# Side_1_v1_1.net
KiCad netlist of a schematic drawn in EAGLE
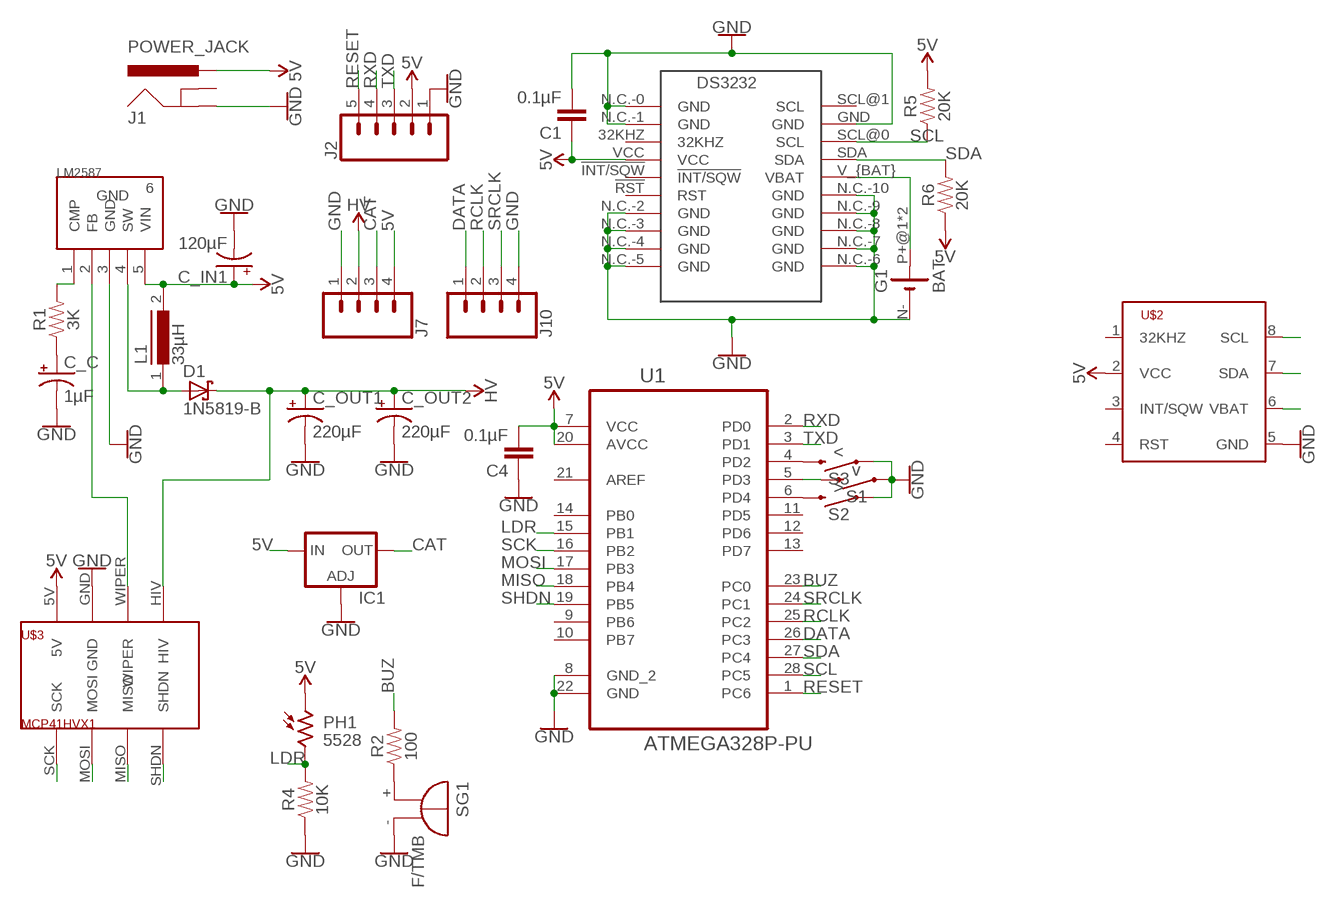
[diagram p0: schematic, sheet 1]

(export (version "E")
  (design (tool "Eeschema 10.0.6"))
  (components
    (comp (ref "C1")
      (value "0.1µF")
      (footprint "eagle-import:CAP-0.1I")
      (libsource (lib "eagle-import") (part "0.1µF-0.1''"))
    )
    (comp (ref "C4")
      (value "0.1µF")
      (footprint "eagle-import:CAP-0.1I")
      (libsource (lib "eagle-import") (part "0.1µF-0.1''"))
    )
    (comp (ref "C_C")
      (value "1µF")
      (footprint "eagle-import:CAP_POL_2MM")
      (libsource (lib "eagle-import") (part "CAP_POL_1µF"))
    )
    (comp (ref "C_IN1")
      (value "120µF")
      (footprint "eagle-import:CAP_POL_3MM")
      (libsource (lib "eagle-import") (part "CAP_POL_120µF"))
    )
    (comp (ref "C_OUT1")
      (value "220µF")
      (footprint "eagle-import:CPOL-RADIAL-5MM-10MM")
      (libsource (lib "eagle-import") (part "1000UF-RADIAL-5MM-25V-20%"))
    )
    (comp (ref "C_OUT2")
      (value "220µF")
      (footprint "eagle-import:CPOL-RADIAL-5MM-10MM")
      (libsource (lib "eagle-import") (part "1000UF-RADIAL-5MM-25V-20%"))
    )
    (comp (ref "D1")
      (value "1N5819-B")
      (footprint "eagle-import:DO41-7.6")
      (libsource (lib "eagle-import") (part "1N5819-B"))
    )
    (comp (ref "G1")
      (value "BAT")
      (footprint "eagle-import:CELL_RETAINER_11.6MM")
      (fields (field (name "MF") "KEYSTONE") (field (name "MPN") "2997"))
      (libsource (lib "eagle-import") (part "BATTERY-HOLDER_11.6MM"))
    )
    (comp (ref "IC1")
      (value "LM317TS")
      (footprint "eagle-import:317TS")
      (libsource (lib "eagle-import") (part "LM317TS"))
    )
    (comp (ref "J1")
      (value "POWER_JACK")
      (footprint "eagle-import:POWER_JACK_PTH")
      (libsource (lib "eagle-import") (part "POWER_JACK"))
    )
    (comp (ref "J2")
      (value "CONN_05")
      (footprint "eagle-import:1X05")
      (libsource (lib "eagle-import") (part "CONN_05"))
    )
    (comp (ref "J7")
      (value "CONN_04")
      (footprint "eagle-import:1X04")
      (libsource (lib "eagle-import") (part "CONN_04"))
    )
    (comp (ref "J10")
      (value "CONN_04")
      (footprint "eagle-import:1X04")
      (libsource (lib "eagle-import") (part "CONN_04"))
    )
    (comp (ref "L1")
      (value "33µH")
      (footprint "eagle-import:MICC12")
      (libsource (lib "eagle-import") (part "MICC12"))
    )
    (comp (ref "LM2587")
      (value "LM2587S")
      (footprint "eagle-import:TO263-5")
      (libsource (lib "eagle-import") (part "LM2587S"))
    )
    (comp (ref "PH1")
      (value "5528")
      (footprint "eagle-import:5528")
      (libsource (lib "eagle-import") (part "5528"))
    )
    (comp (ref "R1")
      (value "3K")
      (footprint "eagle-import:AXIAL-0.3")
      (libsource (lib "eagle-import") (part "RESISTORAXIAL-0.3"))
    )
    (comp (ref "R2")
      (value "100")
      (footprint "eagle-import:AXIAL-0.3")
      (libsource (lib "eagle-import") (part "RESISTORAXIAL-0.3"))
    )
    (comp (ref "R4")
      (value "10K")
      (footprint "eagle-import:AXIAL-0.3")
      (libsource (lib "eagle-import") (part "RESISTORAXIAL-0.3"))
    )
    (comp (ref "R5")
      (value "20K")
      (footprint "eagle-import:AXIAL-0.3")
      (libsource (lib "eagle-import") (part "RESISTORAXIAL-0.3"))
    )
    (comp (ref "R6")
      (value "20K")
      (footprint "eagle-import:AXIAL-0.3")
      (libsource (lib "eagle-import") (part "RESISTORAXIAL-0.3"))
    )
    (comp (ref "S1")
      (value "v")
      (footprint "eagle-import:TACTILE_SWITCH_PTH_6.0MM")
      (libsource (lib "eagle-import") (part "MOMENTARY-SWITCH-SPST-PTH-6.0MM"))
    )
    (comp (ref "S2")
      (value ">")
      (footprint "eagle-import:TACTILE_SWITCH_PTH_6.0MM")
      (libsource (lib "eagle-import") (part "MOMENTARY-SWITCH-SPST-PTH-6.0MM"))
    )
    (comp (ref "S3")
      (value "<")
      (footprint "eagle-import:TACTILE_SWITCH_PTH_6.0MM")
      (libsource (lib "eagle-import") (part "MOMENTARY-SWITCH-SPST-PTH-6.0MM"))
    )
    (comp (ref "SG1")
      (value "F/TMB")
      (footprint "eagle-import:F_TMB")
      (libsource (lib "eagle-import") (part "F/TMB"))
    )
    (comp (ref "U$1")
      (value "DS3232")
      (footprint "eagle-import:SO20-2")
      (libsource (lib "eagle-import") (part "DS3232"))
    )
    (comp (ref "U$2")
      (value "DS3232M")
      (footprint "eagle-import:SO8")
      (libsource (lib "eagle-import") (part "DS3232M"))
    )
    (comp (ref "U$3")
      (value "MCP41HVX1")
      (footprint "eagle-import:MCP41HVX1_BREAKOUT")
      (libsource (lib "eagle-import") (part "MCP41HVX1_BREAKOUT"))
    )
    (comp (ref "U1")
      (value "ATMEGA328P-PU")
      (footprint "eagle-import:DIP254P762X457-28")
      (libsource (lib "eagle-import") (part "ATMEGA328P-PU"))
    )
  )
  (nets
    (net (code "1") (name "/BAT") (class "Default")
      (node (ref "G1") (pin "P+@1") (pinfunction "+_P+@1") (pintype "passive"))
      (node (ref "G1") (pin "P+@2") (pinfunction "+_P+@2") (pintype "passive"))
      (node (ref "U$1") (pin "V_{BAT}") (pinfunction "VBAT_V_{BAT}") (pintype "bidirectional"))
      (node (ref "U$2") (pin "6") (pinfunction "VBAT_6") (pintype "bidirectional"))
    )
    (net (code "2") (name "/BUZ") (class "Default")
      (node (ref "R2") (pin "P$2") (pinfunction "2_P$2") (pintype "passive"))
      (node (ref "U1") (pin "23") (pinfunction "PC0_23") (pintype "bidirectional"))
    )
    (net (code "3") (name "/CAT") (class "Default")
      (node (ref "IC1") (pin "2") (pinfunction "OUT_2") (pintype "passive"))
      (node (ref "J7") (pin "3") (pinfunction "3_3") (pintype "passive"))
    )
    (net (code "4") (name "/DATA") (class "Default")
      (node (ref "J10") (pin "1") (pinfunction "1_1") (pintype "passive"))
      (node (ref "U1") (pin "26") (pinfunction "PC3_26") (pintype "bidirectional"))
    )
    (net (code "5") (name "/LDR") (class "Default")
      (node (ref "PH1") (pin "2") (pinfunction "2_2") (pintype "passive"))
      (node (ref "R4") (pin "P$2") (pinfunction "2_P$2") (pintype "passive"))
      (node (ref "U1") (pin "15") (pinfunction "PB1_15") (pintype "bidirectional"))
    )
    (net (code "6") (name "/MISO") (class "Default")
      (node (ref "U$3") (pin "MISO") (pinfunction "MISO_MISO") (pintype "bidirectional"))
      (node (ref "U1") (pin "18") (pinfunction "PB4_18") (pintype "bidirectional"))
    )
    (net (code "7") (name "/MOSI") (class "Default")
      (node (ref "U$3") (pin "MOSI") (pinfunction "MOSI_MOSI") (pintype "bidirectional"))
      (node (ref "U1") (pin "17") (pinfunction "PB3_17") (pintype "bidirectional"))
    )
    (net (code "8") (name "/RCLK") (class "Default")
      (node (ref "J10") (pin "2") (pinfunction "2_2") (pintype "passive"))
      (node (ref "U1") (pin "25") (pinfunction "PC2_25") (pintype "bidirectional"))
    )
    (net (code "9") (name "/RESET") (class "Default")
      (node (ref "J2") (pin "5") (pinfunction "5_5") (pintype "passive"))
      (node (ref "U1") (pin "1") (pinfunction "PC6_1") (pintype "bidirectional"))
    )
    (net (code "10") (name "/RXD") (class "Default")
      (node (ref "J2") (pin "4") (pinfunction "4_4") (pintype "passive"))
      (node (ref "U1") (pin "2") (pinfunction "PD0_2") (pintype "bidirectional"))
    )
    (net (code "11") (name "/SCK") (class "Default")
      (node (ref "U$3") (pin "SCK") (pinfunction "SCK_SCK") (pintype "bidirectional"))
      (node (ref "U1") (pin "16") (pinfunction "PB2_16") (pintype "bidirectional"))
    )
    (net (code "12") (name "/SCL") (class "Default")
      (node (ref "R5") (pin "P$1") (pinfunction "1_P$1") (pintype "passive"))
      (node (ref "U$1") (pin "SCL@0") (pinfunction "SCL_SCL@0") (pintype "bidirectional"))
      (node (ref "U$2") (pin "8") (pinfunction "SCL_8") (pintype "bidirectional"))
      (node (ref "U1") (pin "28") (pinfunction "PC5_28") (pintype "bidirectional"))
    )
    (net (code "13") (name "/SDA") (class "Default")
      (node (ref "R6") (pin "P$2") (pinfunction "2_P$2") (pintype "passive"))
      (node (ref "U$1") (pin "SDA") (pinfunction "SDA_SDA") (pintype "bidirectional"))
      (node (ref "U$2") (pin "7") (pinfunction "SDA_7") (pintype "bidirectional"))
      (node (ref "U1") (pin "27") (pinfunction "PC4_27") (pintype "bidirectional"))
    )
    (net (code "14") (name "/SHDN") (class "Default")
      (node (ref "U$3") (pin "SHDN") (pinfunction "SHDN_SHDN") (pintype "bidirectional"))
      (node (ref "U1") (pin "19") (pinfunction "PB5_19") (pintype "bidirectional"))
    )
    (net (code "15") (name "/SRCLK") (class "Default")
      (node (ref "J10") (pin "3") (pinfunction "3_3") (pintype "passive"))
      (node (ref "U1") (pin "24") (pinfunction "PC1_24") (pintype "bidirectional"))
    )
    (net (code "16") (name "/TXD") (class "Default")
      (node (ref "J2") (pin "3") (pinfunction "3_3") (pintype "passive"))
      (node (ref "U1") (pin "3") (pinfunction "PD1_3") (pintype "bidirectional"))
    )
    (net (code "17") (name "5V") (class "Default")
      (node (ref "C1") (pin "1") (pinfunction "1_1") (pintype "passive"))
      (node (ref "C4") (pin "2") (pinfunction "2_2") (pintype "passive"))
      (node (ref "C_IN1") (pin "POS") (pinfunction "+_POS") (pintype "passive"))
      (node (ref "IC1") (pin "3") (pinfunction "IN_3") (pintype "input"))
      (node (ref "J1") (pin "PWR") (pinfunction "PWR_PWR") (pintype "bidirectional"))
      (node (ref "J2") (pin "2") (pinfunction "2_2") (pintype "passive"))
      (node (ref "J7") (pin "4") (pinfunction "4_4") (pintype "passive"))
      (node (ref "L1") (pin "2") (pinfunction "2_2") (pintype "passive"))
      (node (ref "LM2587") (pin "5") (pinfunction "VIN_5") (pintype "bidirectional"))
      (node (ref "PH1") (pin "1") (pinfunction "1_1") (pintype "passive"))
      (node (ref "R5") (pin "P$2") (pinfunction "2_P$2") (pintype "passive"))
      (node (ref "R6") (pin "P$1") (pinfunction "1_P$1") (pintype "passive"))
      (node (ref "U$1") (pin "VCC") (pinfunction "VCC_VCC") (pintype "bidirectional"))
      (node (ref "U$2") (pin "2") (pinfunction "VCC_2") (pintype "bidirectional"))
      (node (ref "U$3") (pin "5V") (pinfunction "5V_5V") (pintype "bidirectional"))
      (node (ref "U1") (pin "20") (pinfunction "AVCC_20") (pintype "power_in"))
      (node (ref "U1") (pin "7") (pinfunction "VCC_7") (pintype "power_in"))
    )
    (net (code "18") (name "GND") (class "Default")
      (node (ref "C1") (pin "2") (pinfunction "2_2") (pintype "passive"))
      (node (ref "C4") (pin "1") (pinfunction "1_1") (pintype "passive"))
      (node (ref "C_C") (pin "NEG") (pinfunction "-_NEG") (pintype "passive"))
      (node (ref "C_IN1") (pin "NEG") (pinfunction "-_NEG") (pintype "passive"))
      (node (ref "C_OUT1") (pin "-") (pinfunction "-_-") (pintype "passive"))
      (node (ref "C_OUT2") (pin "-") (pinfunction "-_-") (pintype "passive"))
      (node (ref "G1") (pin "N-") (pinfunction "-_N-") (pintype "passive"))
      (node (ref "IC1") (pin "1") (pinfunction "ADJ_1") (pintype "input"))
      (node (ref "J1") (pin "GND") (pinfunction "GND_GND") (pintype "bidirectional"))
      (node (ref "J10") (pin "4") (pinfunction "4_4") (pintype "passive"))
      (node (ref "J2") (pin "1") (pinfunction "1_1") (pintype "passive"))
      (node (ref "J7") (pin "1") (pinfunction "1_1") (pintype "passive"))
      (node (ref "LM2587") (pin "3") (pinfunction "GND_3") (pintype "bidirectional"))
      (node (ref "R4") (pin "P$1") (pinfunction "1_P$1") (pintype "passive"))
      (node (ref "S1") (pin "1") (pinfunction "1_1") (pintype "passive"))
      (node (ref "S2") (pin "1") (pinfunction "1_1") (pintype "passive"))
      (node (ref "S3") (pin "1") (pinfunction "1_1") (pintype "passive"))
      (node (ref "SG1") (pin "-") (pinfunction "-_-") (pintype "passive"))
      (node (ref "U$1") (pin "GND") (pinfunction "GND_GND") (pintype "bidirectional"))
      (node (ref "U$1") (pin "N.C.-0") (pinfunction "GND_N.C.-0") (pintype "bidirectional"))
      (node (ref "U$1") (pin "N.C.-1") (pinfunction "GND_N.C.-1") (pintype "bidirectional"))
      (node (ref "U$1") (pin "N.C.-10") (pinfunction "GND_N.C.-10") (pintype "bidirectional"))
      (node (ref "U$1") (pin "N.C.-2") (pinfunction "GND_N.C.-2") (pintype "bidirectional"))
      (node (ref "U$1") (pin "N.C.-3") (pinfunction "GND_N.C.-3") (pintype "bidirectional"))
      (node (ref "U$1") (pin "N.C.-4") (pinfunction "GND_N.C.-4") (pintype "bidirectional"))
      (node (ref "U$1") (pin "N.C.-5") (pinfunction "GND_N.C.-5") (pintype "bidirectional"))
      (node (ref "U$1") (pin "N.C.-6") (pinfunction "GND_N.C.-6") (pintype "bidirectional"))
      (node (ref "U$1") (pin "N.C.-7") (pinfunction "GND_N.C.-7") (pintype "bidirectional"))
      (node (ref "U$1") (pin "N.C.-8") (pinfunction "GND_N.C.-8") (pintype "bidirectional"))
      (node (ref "U$1") (pin "N.C.-9") (pinfunction "GND_N.C.-9") (pintype "bidirectional"))
      (node (ref "U$2") (pin "5") (pinfunction "GND_5") (pintype "bidirectional"))
      (node (ref "U$3") (pin "GND") (pinfunction "GND_GND") (pintype "bidirectional"))
      (node (ref "U1") (pin "22") (pinfunction "GND_22") (pintype "passive"))
      (node (ref "U1") (pin "8") (pinfunction "GND_2_8") (pintype "passive"))
    )
    (net (code "19") (name "HV") (class "Default")
      (node (ref "C_OUT1") (pin "+") (pinfunction "+_+") (pintype "passive"))
      (node (ref "C_OUT2") (pin "+") (pinfunction "+_+") (pintype "passive"))
      (node (ref "D1") (pin "C") (pinfunction "C_C") (pintype "passive"))
      (node (ref "J7") (pin "2") (pinfunction "2_2") (pintype "passive"))
      (node (ref "U$3") (pin "HIV") (pinfunction "HIV_HIV") (pintype "bidirectional"))
    )
    (net (code "20") (name "Net-(C_C-+)") (class "Default")
      (node (ref "C_C") (pin "POS") (pinfunction "+_POS") (pintype "passive"))
      (node (ref "R1") (pin "P$1") (pinfunction "1_P$1") (pintype "passive"))
    )
    (net (code "21") (name "Net-(LM2587-CMP)") (class "Default")
      (node (ref "LM2587") (pin "1") (pinfunction "CMP_1") (pintype "bidirectional"))
      (node (ref "R1") (pin "P$2") (pinfunction "2_P$2") (pintype "passive"))
    )
    (net (code "22") (name "Net-(LM2587-FB)") (class "Default")
      (node (ref "LM2587") (pin "2") (pinfunction "FB_2") (pintype "bidirectional"))
      (node (ref "U$3") (pin "WIPER") (pinfunction "WIPER_WIPER") (pintype "bidirectional"))
    )
    (net (code "23") (name "Net-(LM2587-SW)") (class "Default")
      (node (ref "D1") (pin "A") (pinfunction "A_A") (pintype "passive"))
      (node (ref "L1") (pin "1") (pinfunction "1_1") (pintype "passive"))
      (node (ref "LM2587") (pin "4") (pinfunction "SW_4") (pintype "bidirectional"))
    )
    (net (code "24") (name "Net-(R2-1)") (class "Default")
      (node (ref "R2") (pin "P$1") (pinfunction "1_P$1") (pintype "passive"))
      (node (ref "SG1") (pin "+") (pinfunction "+_+") (pintype "passive"))
    )
    (net (code "25") (name "Net-(S1-2)") (class "Default")
      (node (ref "S1") (pin "3") (pinfunction "2_3") (pintype "passive"))
      (node (ref "U1") (pin "5") (pinfunction "PD3_5") (pintype "bidirectional"))
    )
    (net (code "26") (name "Net-(S2-2)") (class "Default")
      (node (ref "S2") (pin "3") (pinfunction "2_3") (pintype "passive"))
      (node (ref "U1") (pin "6") (pinfunction "PD4_6") (pintype "bidirectional"))
    )
    (net (code "27") (name "Net-(S3-2)") (class "Default")
      (node (ref "S3") (pin "3") (pinfunction "2_3") (pintype "passive"))
      (node (ref "U1") (pin "4") (pinfunction "PD2_4") (pintype "bidirectional"))
    )
    (net (code "28") (name "unconnected-(J1-PadGNDBREAK)") (class "Default")
      (node (ref "J1") (pin "GNDBREAK") (pinfunction "GNDBREAK_GNDBREAK") (pintype "bidirectional"))
    )
    (net (code "29") (name "unconnected-(LM2587-GND-Pad6)") (class "Default")
      (node (ref "LM2587") (pin "6") (pinfunction "GND_6") (pintype "bidirectional"))
    )
    (net (code "30") (name "unconnected-(U$1-Pad32KHZ)") (class "Default")
      (node (ref "U$1") (pin "32KHZ") (pinfunction "32KHZ_32KHZ") (pintype "bidirectional"))
    )
    (net (code "31") (name "unconnected-(U$1-RST-Pad!RST)") (class "Default")
      (node (ref "U$1") (pin "!RST") (pinfunction "RST_!RST") (pintype "bidirectional"))
    )
    (net (code "32") (name "unconnected-(U$1-SCL-PadSCL@1)") (class "Default")
      (node (ref "U$1") (pin "SCL@1") (pinfunction "SCL_SCL@1") (pintype "bidirectional"))
    )
    (net (code "33") (name "unconnected-(U$1-~{INT{slash}SQW}-Pad!INT{slash}SQW)") (class "Default")
      (node (ref "U$1") (pin "!INT/SQW") (pinfunction "~{INT/SQW}_!INT/SQW") (pintype "bidirectional"))
    )
    (net (code "34") (name "unconnected-(U$2-32KHZ-Pad1)") (class "Default")
      (node (ref "U$2") (pin "1") (pinfunction "32KHZ_1") (pintype "bidirectional"))
    )
    (net (code "35") (name "unconnected-(U$2-INT{slash}SQW-Pad3)") (class "Default")
      (node (ref "U$2") (pin "3") (pinfunction "INT/SQW_3") (pintype "bidirectional"))
    )
    (net (code "36") (name "unconnected-(U$2-RST-Pad4)") (class "Default")
      (node (ref "U$2") (pin "4") (pinfunction "RST_4") (pintype "bidirectional"))
    )
    (net (code "37") (name "unconnected-(U1-AREF-Pad21)") (class "Default")
      (node (ref "U1") (pin "21") (pinfunction "AREF_21") (pintype "input"))
    )
    (net (code "38") (name "unconnected-(U1-PB0-Pad14)") (class "Default")
      (node (ref "U1") (pin "14") (pinfunction "PB0_14") (pintype "bidirectional"))
    )
    (net (code "39") (name "unconnected-(U1-PB6-Pad9)") (class "Default")
      (node (ref "U1") (pin "9") (pinfunction "PB6_9") (pintype "bidirectional"))
    )
    (net (code "40") (name "unconnected-(U1-PB7-Pad10)") (class "Default")
      (node (ref "U1") (pin "10") (pinfunction "PB7_10") (pintype "bidirectional"))
    )
    (net (code "41") (name "unconnected-(U1-PD5-Pad11)") (class "Default")
      (node (ref "U1") (pin "11") (pinfunction "PD5_11") (pintype "bidirectional"))
    )
    (net (code "42") (name "unconnected-(U1-PD6-Pad12)") (class "Default")
      (node (ref "U1") (pin "12") (pinfunction "PD6_12") (pintype "bidirectional"))
    )
    (net (code "43") (name "unconnected-(U1-PD7-Pad13)") (class "Default")
      (node (ref "U1") (pin "13") (pinfunction "PD7_13") (pintype "bidirectional"))
    )
  )
)
